# Sh2_MCU.net
KiCad netlist of a schematic drawn in Altium Designer
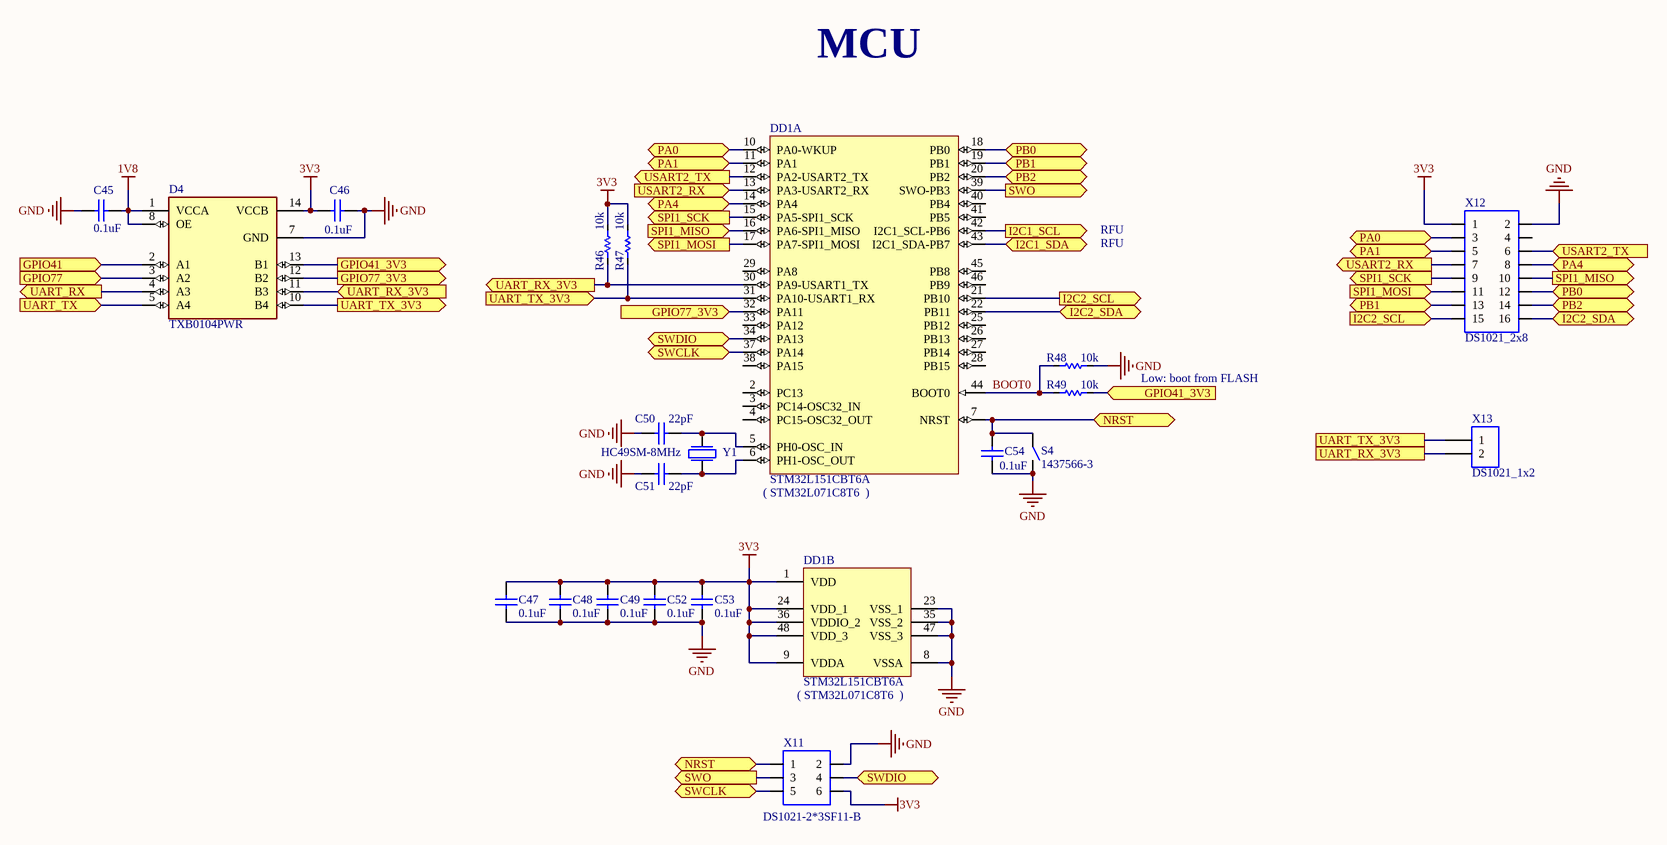
[diagram p0: Sh2_MCU.SchDoc]

(export (version "E")
  (design (tool "Eeschema 10.0.6"))
  (components
    (comp (ref "C45")
      (value "0.1uF")
      (footprint "C_SMD0603")
      (description "GRM188R71H104KA93D")
      (libsource (lib "MyCompLib") (part "C_SMD"))
    )
    (comp (ref "C46")
      (value "0.1uF")
      (footprint "C_SMD0603")
      (description "GRM188R71H104KA93D")
      (libsource (lib "MyCompLib") (part "C_SMD"))
    )
    (comp (ref "C47")
      (value "0.1uF")
      (footprint "C_SMD0603")
      (description "GRM188R71H104KA93D")
      (libsource (lib "MyCompLib") (part "C_SMD"))
    )
    (comp (ref "C48")
      (value "0.1uF")
      (footprint "C_SMD0603")
      (description "GRM188R71H104KA93D")
      (libsource (lib "MyCompLib") (part "C_SMD"))
    )
    (comp (ref "C49")
      (value "0.1uF")
      (footprint "C_SMD0603")
      (description "GRM188R71H104KA93D")
      (libsource (lib "MyCompLib") (part "C_SMD"))
    )
    (comp (ref "C50")
      (value "22pF")
      (footprint "C_SMD0603")
      (description "GRM1885C1H220JA01D")
      (libsource (lib "MyCompLib") (part "C_SMD"))
    )
    (comp (ref "C51")
      (value "22pF")
      (footprint "C_SMD0603")
      (description "GRM1885C1H220JA01D")
      (libsource (lib "MyCompLib") (part "C_SMD"))
    )
    (comp (ref "C52")
      (value "0.1uF")
      (footprint "C_SMD0603")
      (description "GRM188R71H104KA93D")
      (libsource (lib "MyCompLib") (part "C_SMD"))
    )
    (comp (ref "C53")
      (value "0.1uF")
      (footprint "C_SMD0603")
      (description "GRM188R71H104KA93D")
      (libsource (lib "MyCompLib") (part "C_SMD"))
    )
    (comp (ref "C54")
      (value "0.1uF")
      (footprint "C_SMD0603")
      (description "GRM188R71H104KA93D")
      (libsource (lib "MyCompLib") (part "C_SMD"))
    )
    (comp (ref "D4")
      (value "TXB0104PWR")
      (footprint "SOP65P640X120-14N")
      (fields (field (name "MF") "Texas Instruments"))
      (libsource (lib "MyCompLib") (part "TXB0104PWR"))
    )
    (comp (ref "DD1")
      (value "STM32L151CBT6A")
      (footprint "LQFP48_N")
      (fields (field (name "PARTNUMBER") "STM32F103C8T6"))
      (libsource (lib "MyCompLib") (part "STM32L151CBT6A"))
    )
    (comp (ref "R46")
      (value "10k")
      (footprint "R_SMD0603")
      (description "RC0603FR-0710KL (CRCW060310K0FKEA)")
      (libsource (lib "MyCompLib") (part "R_SMD"))
    )
    (comp (ref "R47")
      (value "10k")
      (footprint "R_SMD0603")
      (description "RC0603FR-0710KL (CRCW060310K0FKEA)")
      (libsource (lib "MyCompLib") (part "R_SMD"))
    )
    (comp (ref "R48")
      (value "10k")
      (footprint "R_SMD0603")
      (description "RC0603FR-0710KL (CRCW060310K0FKEA)")
      (libsource (lib "MyCompLib") (part "R_SMD"))
    )
    (comp (ref "R49")
      (value "10k")
      (footprint "R_SMD0603")
      (description "RC0603FR-0710KL (CRCW060310K0FKEA)")
      (libsource (lib "MyCompLib") (part "R_SMD"))
    )
    (comp (ref "S4")
      (value "1437566-3")
      (footprint "1437566-3")
      (description "SMD button")
      (libsource (lib "MyCompLib") (part "1437566-3"))
    )
    (comp (ref "X11")
      (value "DS1021-2*3SF11-B")
      (footprint "PLD2-3")
      (description "Вилка штыревая 2.54мм 2x3 прямая тип1")
      (libsource (lib "MyCompLib") (part "DS1021_2x3"))
    )
    (comp (ref "X12")
      (value "DS1021_2x8")
      (footprint "PLD2X8")
      (description "Вилка штыревая 2.54мм 2х8 прямая PLD-16")
      (libsource (lib "MyCompLib") (part "DS1021_2x8"))
    )
    (comp (ref "X13")
      (value "DS1021_1x2")
      (footprint "PLD2")
      (description "Вилка штыревая 2.54мм 1x2 прямая PLS-2")
      (libsource (lib "MyCompLib") (part "DS1021_1x2"))
    )
    (comp (ref "Y1")
      (value "HC49SM-8MHz")
      (footprint "HC49SM")
      (description "8 MHz resonator")
      (libsource (lib "MyCompLib") (part "HC49SM"))
    )
  )
  (nets
    (net (code "1") (name "/BOOT0") (class "Default")
      (node (ref "DD1") (pin "44") (pinfunction "BOOT0_44") (pintype "input"))
      (node (ref "R48") (pin "1") (pinfunction "CCW_1") (pintype "passive"))
      (node (ref "R49") (pin "1") (pinfunction "CCW_1") (pintype "passive"))
    )
    (net (code "2") (name "/GPIO41") (class "Default")
      (node (ref "D4") (pin "2") (pinfunction "A1_2") (pintype "bidirectional"))
    )
    (net (code "3") (name "/GPIO41_3V3") (class "Default")
      (node (ref "D4") (pin "13") (pinfunction "B1_13") (pintype "bidirectional"))
      (node (ref "R49") (pin "2") (pinfunction "CW_2") (pintype "passive"))
    )
    (net (code "4") (name "/GPIO77") (class "Default")
      (node (ref "D4") (pin "3") (pinfunction "A2_3") (pintype "bidirectional"))
    )
    (net (code "5") (name "/GPIO77_3V3") (class "Default")
      (node (ref "D4") (pin "12") (pinfunction "B2_12") (pintype "bidirectional"))
      (node (ref "DD1") (pin "32") (pinfunction "PA11_32") (pintype "bidirectional"))
    )
    (net (code "6") (name "/I2C1_SCL") (class "Default")
      (node (ref "DD1") (pin "42") (pinfunction "I2C1_SCL-PB6_42") (pintype "bidirectional"))
    )
    (net (code "7") (name "/I2C1_SDA") (class "Default")
      (node (ref "DD1") (pin "43") (pinfunction "I2C1_SDA-PB7_43") (pintype "bidirectional"))
    )
    (net (code "8") (name "/I2C2_SCL") (class "Default")
      (node (ref "DD1") (pin "21") (pinfunction "PB10_21") (pintype "bidirectional"))
      (node (ref "X12") (pin "15") (pinfunction "15_15") (pintype "passive"))
    )
    (net (code "9") (name "/I2C2_SDA") (class "Default")
      (node (ref "DD1") (pin "22") (pinfunction "PB11_22") (pintype "bidirectional"))
      (node (ref "X12") (pin "16") (pinfunction "16_16") (pintype "passive"))
    )
    (net (code "10") (name "/NRST") (class "Default")
      (node (ref "C54") (pin "1") (pinfunction "1_1") (pintype "passive"))
      (node (ref "DD1") (pin "7") (pinfunction "NRST_7") (pintype "bidirectional"))
      (node (ref "S4") (pin "1") (pinfunction "1_1") (pintype "passive"))
      (node (ref "X11") (pin "1") (pinfunction "1_1") (pintype "passive"))
    )
    (net (code "11") (name "/PA0") (class "Default")
      (node (ref "DD1") (pin "10") (pinfunction "PA0-WKUP_10") (pintype "bidirectional"))
      (node (ref "X12") (pin "3") (pinfunction "3_3") (pintype "passive"))
    )
    (net (code "12") (name "/PA1") (class "Default")
      (node (ref "DD1") (pin "11") (pinfunction "PA1_11") (pintype "bidirectional"))
      (node (ref "X12") (pin "5") (pinfunction "5_5") (pintype "passive"))
    )
    (net (code "13") (name "/PA4") (class "Default")
      (node (ref "DD1") (pin "14") (pinfunction "PA4_14") (pintype "bidirectional"))
      (node (ref "X12") (pin "8") (pinfunction "8_8") (pintype "passive"))
    )
    (net (code "14") (name "/PB0") (class "Default")
      (node (ref "DD1") (pin "18") (pinfunction "PB0_18") (pintype "bidirectional"))
      (node (ref "X12") (pin "12") (pinfunction "12_12") (pintype "passive"))
    )
    (net (code "15") (name "/PB1") (class "Default")
      (node (ref "DD1") (pin "19") (pinfunction "PB1_19") (pintype "bidirectional"))
      (node (ref "X12") (pin "13") (pinfunction "13_13") (pintype "passive"))
    )
    (net (code "16") (name "/PB2") (class "Default")
      (node (ref "DD1") (pin "20") (pinfunction "PB2_20") (pintype "bidirectional"))
      (node (ref "X12") (pin "14") (pinfunction "14_14") (pintype "passive"))
    )
    (net (code "17") (name "/SPI1_MISO") (class "Default")
      (node (ref "DD1") (pin "16") (pinfunction "PA6-SPI1_MISO_16") (pintype "bidirectional"))
      (node (ref "X12") (pin "10") (pinfunction "10_10") (pintype "passive"))
    )
    (net (code "18") (name "/SPI1_MOSI") (class "Default")
      (node (ref "DD1") (pin "17") (pinfunction "PA7-SPI1_MOSI_17") (pintype "bidirectional"))
      (node (ref "X12") (pin "11") (pinfunction "11_11") (pintype "passive"))
    )
    (net (code "19") (name "/SPI1_SCK") (class "Default")
      (node (ref "DD1") (pin "15") (pinfunction "PA5-SPI1_SCK_15") (pintype "bidirectional"))
      (node (ref "X12") (pin "9") (pinfunction "9_9") (pintype "passive"))
    )
    (net (code "20") (name "/SWCLK") (class "Default")
      (node (ref "DD1") (pin "37") (pinfunction "PA14_37") (pintype "bidirectional"))
      (node (ref "X11") (pin "5") (pinfunction "5_5") (pintype "passive"))
    )
    (net (code "21") (name "/SWDIO") (class "Default")
      (node (ref "DD1") (pin "34") (pinfunction "PA13_34") (pintype "bidirectional"))
      (node (ref "X11") (pin "4") (pinfunction "4_4") (pintype "passive"))
    )
    (net (code "22") (name "/SWO") (class "Default")
      (node (ref "DD1") (pin "39") (pinfunction "SWO-PB3_39") (pintype "bidirectional"))
      (node (ref "X11") (pin "3") (pinfunction "3_3") (pintype "passive"))
    )
    (net (code "23") (name "/UART_RX") (class "Default")
      (node (ref "D4") (pin "4") (pinfunction "A3_4") (pintype "bidirectional"))
    )
    (net (code "24") (name "/UART_RX_3V3") (class "Default")
      (node (ref "D4") (pin "11") (pinfunction "B3_11") (pintype "bidirectional"))
      (node (ref "DD1") (pin "30") (pinfunction "PA9-USART1_TX_30") (pintype "bidirectional"))
      (node (ref "R46") (pin "2") (pinfunction "CW_2") (pintype "passive"))
      (node (ref "X13") (pin "2") (pinfunction "2_2") (pintype "passive"))
    )
    (net (code "25") (name "/UART_TX") (class "Default")
      (node (ref "D4") (pin "5") (pinfunction "A4_5") (pintype "bidirectional"))
    )
    (net (code "26") (name "/UART_TX_3V3") (class "Default")
      (node (ref "D4") (pin "10") (pinfunction "B4_10") (pintype "bidirectional"))
      (node (ref "DD1") (pin "31") (pinfunction "PA10-USART1_RX_31") (pintype "bidirectional"))
      (node (ref "R47") (pin "2") (pinfunction "CW_2") (pintype "passive"))
      (node (ref "X13") (pin "1") (pinfunction "1_1") (pintype "passive"))
    )
    (net (code "27") (name "/USART2_RX") (class "Default")
      (node (ref "DD1") (pin "13") (pinfunction "PA3-USART2_RX_13") (pintype "bidirectional"))
      (node (ref "X12") (pin "7") (pinfunction "7_7") (pintype "passive"))
    )
    (net (code "28") (name "/USART2_TX") (class "Default")
      (node (ref "DD1") (pin "12") (pinfunction "PA2-USART2_TX_12") (pintype "bidirectional"))
      (node (ref "X12") (pin "6") (pinfunction "6_6") (pintype "passive"))
    )
    (net (code "29") (name "1V8") (class "Default")
      (node (ref "C45") (pin "1") (pinfunction "1_1") (pintype "passive"))
      (node (ref "D4") (pin "1") (pinfunction "VCCA_1") (pintype "power_in"))
      (node (ref "D4") (pin "8") (pinfunction "OE_8") (pintype "bidirectional"))
    )
    (net (code "30") (name "3V3") (class "Default")
      (node (ref "C46") (pin "2") (pinfunction "2_2") (pintype "passive"))
      (node (ref "C47") (pin "1") (pinfunction "1_1") (pintype "passive"))
      (node (ref "C48") (pin "1") (pinfunction "1_1") (pintype "passive"))
      (node (ref "C49") (pin "1") (pinfunction "1_1") (pintype "passive"))
      (node (ref "C52") (pin "1") (pinfunction "1_1") (pintype "passive"))
      (node (ref "C53") (pin "1") (pinfunction "1_1") (pintype "passive"))
      (node (ref "D4") (pin "14") (pinfunction "VCCB_14") (pintype "power_in"))
      (node (ref "DD1") (pin "1") (pinfunction "VDD_1") (pintype "power_in"))
      (node (ref "DD1") (pin "24") (pinfunction "VDD_1_24") (pintype "power_in"))
      (node (ref "DD1") (pin "36") (pinfunction "VDDIO_2_36") (pintype "power_in"))
      (node (ref "DD1") (pin "48") (pinfunction "VDD_3_48") (pintype "power_in"))
      (node (ref "DD1") (pin "9") (pinfunction "VDDA_9") (pintype "power_in"))
      (node (ref "R46") (pin "1") (pinfunction "CCW_1") (pintype "passive"))
      (node (ref "R47") (pin "1") (pinfunction "CCW_1") (pintype "passive"))
      (node (ref "X11") (pin "6") (pinfunction "6_6") (pintype "passive"))
      (node (ref "X12") (pin "1") (pinfunction "1_1") (pintype "passive"))
    )
    (net (code "31") (name "GND") (class "Default")
      (node (ref "C45") (pin "2") (pinfunction "2_2") (pintype "passive"))
      (node (ref "C46") (pin "1") (pinfunction "1_1") (pintype "passive"))
      (node (ref "C47") (pin "2") (pinfunction "2_2") (pintype "passive"))
      (node (ref "C48") (pin "2") (pinfunction "2_2") (pintype "passive"))
      (node (ref "C49") (pin "2") (pinfunction "2_2") (pintype "passive"))
      (node (ref "C50") (pin "1") (pinfunction "1_1") (pintype "passive"))
      (node (ref "C51") (pin "1") (pinfunction "1_1") (pintype "passive"))
      (node (ref "C52") (pin "2") (pinfunction "2_2") (pintype "passive"))
      (node (ref "C53") (pin "2") (pinfunction "2_2") (pintype "passive"))
      (node (ref "C54") (pin "2") (pinfunction "2_2") (pintype "passive"))
      (node (ref "D4") (pin "7") (pinfunction "GND_7") (pintype "power_in"))
      (node (ref "DD1") (pin "23") (pinfunction "VSS_1_23") (pintype "power_in"))
      (node (ref "DD1") (pin "35") (pinfunction "VSS_2_35") (pintype "power_in"))
      (node (ref "DD1") (pin "47") (pinfunction "VSS_3_47") (pintype "power_in"))
      (node (ref "DD1") (pin "8") (pinfunction "VSSA_8") (pintype "power_in"))
      (node (ref "R48") (pin "2") (pinfunction "CW_2") (pintype "passive"))
      (node (ref "S4") (pin "2") (pinfunction "2_2") (pintype "passive"))
      (node (ref "X11") (pin "2") (pinfunction "2_2") (pintype "passive"))
      (node (ref "X12") (pin "2") (pinfunction "2_2") (pintype "passive"))
    )
    (net (code "32") (name "Net-(DD1A-PH0-OSC_IN)") (class "Default")
      (node (ref "C50") (pin "2") (pinfunction "2_2") (pintype "passive"))
      (node (ref "DD1") (pin "5") (pinfunction "PH0-OSC_IN_5") (pintype "bidirectional"))
      (node (ref "Y1") (pin "2") (pinfunction "2_2") (pintype "passive"))
    )
    (net (code "33") (name "Net-(DD1A-PH1-OSC_OUT)") (class "Default")
      (node (ref "C51") (pin "2") (pinfunction "2_2") (pintype "passive"))
      (node (ref "DD1") (pin "6") (pinfunction "PH1-OSC_OUT_6") (pintype "bidirectional"))
      (node (ref "Y1") (pin "1") (pinfunction "1_1") (pintype "passive"))
    )
    (net (code "34") (name "unconnected-(DD1A-PA8-Pad29)") (class "Default")
      (node (ref "DD1") (pin "29") (pinfunction "PA8_29") (pintype "bidirectional"))
    )
    (net (code "35") (name "unconnected-(DD1A-PA12-Pad33)") (class "Default")
      (node (ref "DD1") (pin "33") (pinfunction "PA12_33") (pintype "bidirectional"))
    )
    (net (code "36") (name "unconnected-(DD1A-PA15-Pad38)") (class "Default")
      (node (ref "DD1") (pin "38") (pinfunction "PA15_38") (pintype "bidirectional"))
    )
    (net (code "37") (name "unconnected-(DD1A-PB4-Pad40)") (class "Default")
      (node (ref "DD1") (pin "40") (pinfunction "PB4_40") (pintype "bidirectional"))
    )
    (net (code "38") (name "unconnected-(DD1A-PB5-Pad41)") (class "Default")
      (node (ref "DD1") (pin "41") (pinfunction "PB5_41") (pintype "bidirectional"))
    )
    (net (code "39") (name "unconnected-(DD1A-PB8-Pad45)") (class "Default")
      (node (ref "DD1") (pin "45") (pinfunction "PB8_45") (pintype "bidirectional"))
    )
    (net (code "40") (name "unconnected-(DD1A-PB9-Pad46)") (class "Default")
      (node (ref "DD1") (pin "46") (pinfunction "PB9_46") (pintype "bidirectional"))
    )
    (net (code "41") (name "unconnected-(DD1A-PB12-Pad25)") (class "Default")
      (node (ref "DD1") (pin "25") (pinfunction "PB12_25") (pintype "bidirectional"))
    )
    (net (code "42") (name "unconnected-(DD1A-PB13-Pad26)") (class "Default")
      (node (ref "DD1") (pin "26") (pinfunction "PB13_26") (pintype "bidirectional"))
    )
    (net (code "43") (name "unconnected-(DD1A-PB14-Pad27)") (class "Default")
      (node (ref "DD1") (pin "27") (pinfunction "PB14_27") (pintype "bidirectional"))
    )
    (net (code "44") (name "unconnected-(DD1A-PB15-Pad28)") (class "Default")
      (node (ref "DD1") (pin "28") (pinfunction "PB15_28") (pintype "bidirectional"))
    )
    (net (code "45") (name "unconnected-(DD1A-PC13-Pad2)") (class "Default")
      (node (ref "DD1") (pin "2") (pinfunction "PC13_2") (pintype "bidirectional"))
    )
    (net (code "46") (name "unconnected-(DD1A-PC14-OSC32_IN-Pad3)") (class "Default")
      (node (ref "DD1") (pin "3") (pinfunction "PC14-OSC32_IN_3") (pintype "bidirectional"))
    )
    (net (code "47") (name "unconnected-(DD1A-PC15-OSC32_OUT-Pad4)") (class "Default")
      (node (ref "DD1") (pin "4") (pinfunction "PC15-OSC32_OUT_4") (pintype "bidirectional"))
    )
    (net (code "48") (name "unconnected-(X12-Pad4)") (class "Default")
      (node (ref "X12") (pin "4") (pinfunction "4_4") (pintype "passive"))
    )
  )
)
